# Peripheralls_and_power_Supply.net
KiCad netlist of a schematic drawn in Altium Designer
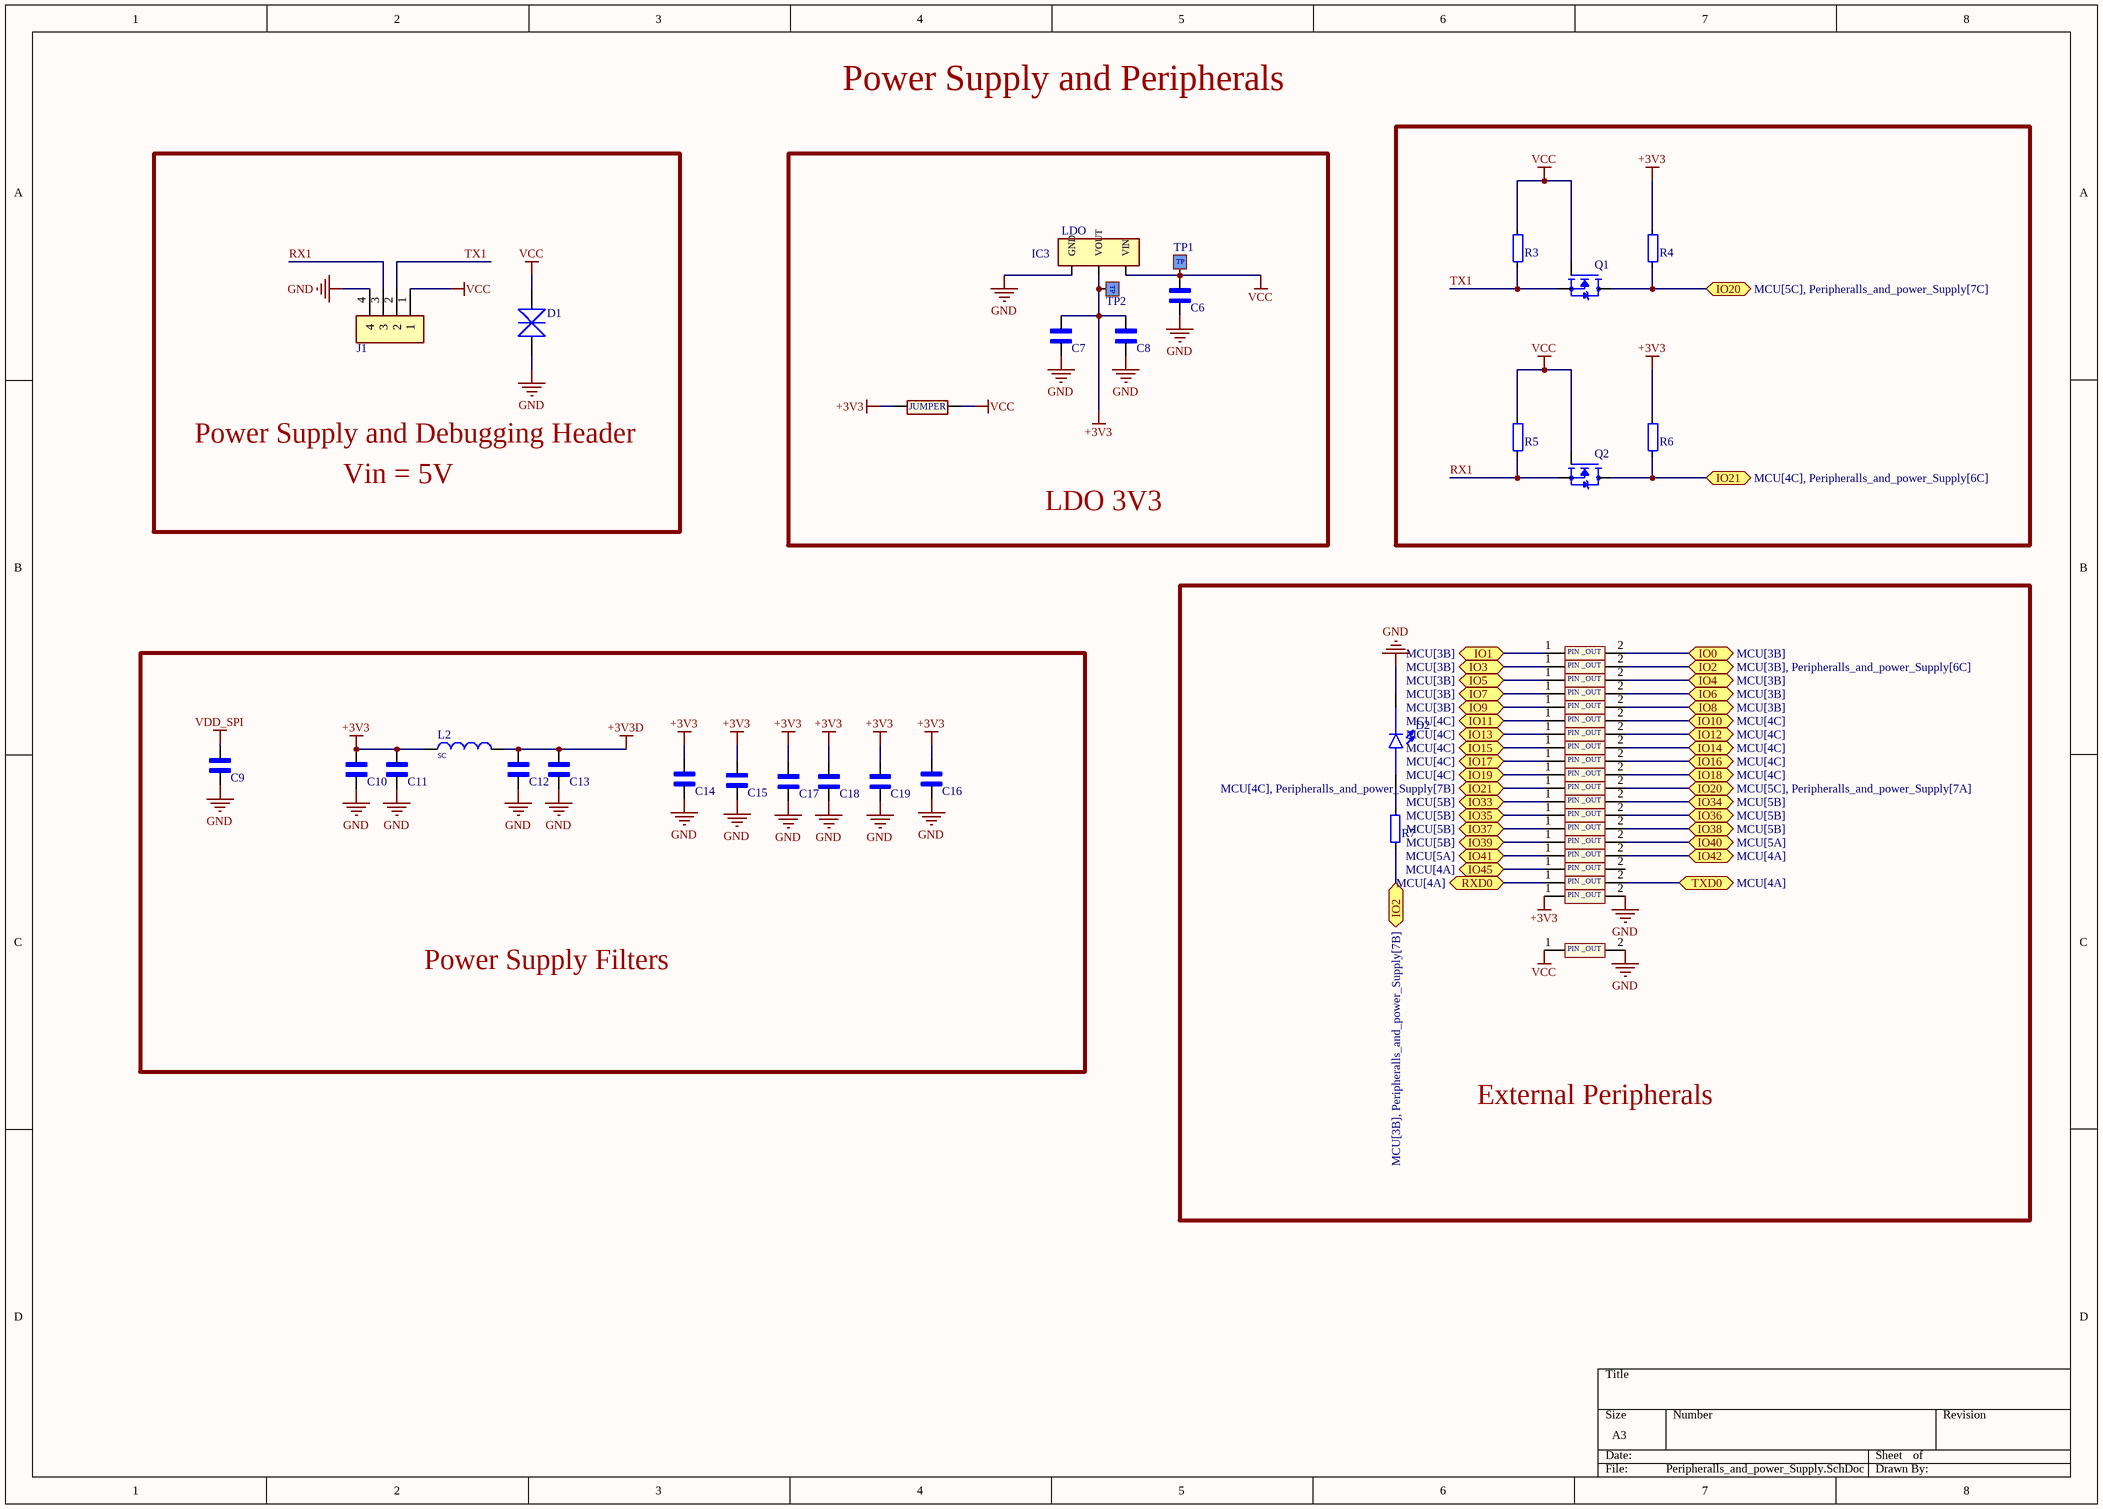
[diagram p0: Peripheralls_and_power_Supply.SchDoc]

(export (version "E")
  (design (tool "Eeschema 10.0.6"))
  (components
    (comp (ref "C6") (value "CAP_0603") (footprint "CAP_0603") (libsource (lib "ESP32-S2") (part "CAP_0603")))
    (comp (ref "C7") (value "CAP_0603") (footprint "CAP_0603") (libsource (lib "") (part "CAP_0603_1")))
    (comp (ref "C8") (value "CAP_0603") (footprint "CAP_0603") (libsource (lib "") (part "CAP_0603_1")))
    (comp (ref "C9") (value "CAP_0603") (footprint "CAP_0603") (libsource (lib "ESP32-S2") (part "CAP_0603")))
    (comp (ref "C10")
      (value "CAP_0603")
      (footprint "CAP_0603")
      (libsource (lib "ESP32-S2") (part "CAP_0603"))
    )
    (comp (ref "C11")
      (value "CAP_0603")
      (footprint "CAP_0603")
      (libsource (lib "ESP32-S2") (part "CAP_0603"))
    )
    (comp (ref "C12")
      (value "CAP_0603")
      (footprint "CAP_0603")
      (libsource (lib "ESP32-S2") (part "CAP_0603"))
    )
    (comp (ref "C13")
      (value "CAP_0603")
      (footprint "CAP_0603")
      (libsource (lib "ESP32-S2") (part "CAP_0603"))
    )
    (comp (ref "C14")
      (value "CAP_0603")
      (footprint "CAP_0603")
      (libsource (lib "ESP32-S2") (part "CAP_0603"))
    )
    (comp (ref "C15")
      (value "CAP_0603")
      (footprint "CAP_0603")
      (libsource (lib "ESP32-S2") (part "CAP_0603"))
    )
    (comp (ref "C16")
      (value "CAP_0603")
      (footprint "CAP_0603")
      (libsource (lib "ESP32-S2") (part "CAP_0603"))
    )
    (comp (ref "C17")
      (value "CAP_0603")
      (footprint "CAP_0603")
      (libsource (lib "ESP32-S2") (part "CAP_0603"))
    )
    (comp (ref "C18")
      (value "CAP_0603")
      (footprint "CAP_0603")
      (libsource (lib "ESP32-S2") (part "CAP_0603"))
    )
    (comp (ref "C19")
      (value "CAP_0603")
      (footprint "CAP_0603")
      (libsource (lib "ESP32-S2") (part "CAP_0603"))
    )
    (comp (ref "D1")
      (value "TVS_DIODE_3.6V")
      (footprint "ESD_DIODE")
      (libsource (lib "ESP32-S2") (part "TVS_DIODE_3.6V"))
    )
    (comp (ref "D2")
      (value "LED0603")
      (footprint "LED0603")
      (description "White LED Indication - Discrete 2.93V 0603 (1608 Metric)")
      (fields (field (name "MF") "Lite-On Inc.") (field (name "MP") "LTW-C191TS5"))
      (libsource (lib "ESP32-S2") (part "LED0603"))
    )
    (comp (ref "IC3")
      (value "LDO")
      (footprint "AMS1117")
      (description "Integrated Circuit")
      (fields (field (name "MANUFACTURER_PART_NUMBER") "AMS1117-3.3"))
      (libsource (lib "ESP32-S2") (part "AMS1117-3.3"))
    )
    (comp (ref "J1")
      (value "S4B-PH-SM4-TB_LF__SN_")
      (footprint "S4B-PH-SM4-TB")
      (description "Connector")
      (fields (field (name "MANUFACTURER_PART_NUMBER") "S4B-PH-SM4-TB(LF)(SN)"))
      (libsource (lib "ESP32-S2") (part "S4B-PH-SM4-TB_LF__SN_"))
    )
    (comp (ref "JU1")
      (value "JUMER")
      (footprint "JUMPER")
      (description "RES_0603")
      (libsource (lib "ESP32-S2") (part "JUMPER"))
    )
    (comp (ref "L2")
      (value "SC")
      (footprint "IND_0402")
      (description "Inductor RF Chip Multi-Layer 2nH 0.3nH 100MHz 8Q-Factor Air 900mA 90mOhm DCR 0402 Automotive T/R")
      (fields (field (name "MP") "LQG15HZ2N0S02D") (field (name "Comment") "IND_0402"))
      (libsource (lib "ESP32-S2") (part "IND_2.0nH_0402"))
    )
    (comp (ref "P1") (value "PIN OUT") (footprint "PIN_OUT") (libsource (lib "ESP32-S2") (part "PIN OUT")))
    (comp (ref "P2") (value "PIN OUT") (footprint "PIN_OUT") (libsource (lib "ESP32-S2") (part "PIN OUT")))
    (comp (ref "P3") (value "PIN OUT") (footprint "PIN_OUT") (libsource (lib "ESP32-S2") (part "PIN OUT")))
    (comp (ref "P4") (value "PIN OUT") (footprint "PIN_OUT") (libsource (lib "ESP32-S2") (part "PIN OUT")))
    (comp (ref "P5") (value "PIN OUT") (footprint "PIN_OUT") (libsource (lib "ESP32-S2") (part "PIN OUT")))
    (comp (ref "P6") (value "PIN OUT") (footprint "PIN_OUT") (libsource (lib "ESP32-S2") (part "PIN OUT")))
    (comp (ref "P7") (value "PIN OUT") (footprint "PIN_OUT") (libsource (lib "ESP32-S2") (part "PIN OUT")))
    (comp (ref "P8") (value "PIN OUT") (footprint "PIN_OUT") (libsource (lib "ESP32-S2") (part "PIN OUT")))
    (comp (ref "P9") (value "PIN OUT") (footprint "PIN_OUT") (libsource (lib "ESP32-S2") (part "PIN OUT")))
    (comp (ref "P10") (value "PIN OUT") (footprint "PIN_OUT") (libsource (lib "ESP32-S2") (part "PIN OUT")))
    (comp (ref "P11") (value "PIN OUT") (footprint "PIN_OUT") (libsource (lib "ESP32-S2") (part "PIN OUT")))
    (comp (ref "P12") (value "PIN OUT") (footprint "PIN_OUT") (libsource (lib "ESP32-S2") (part "PIN OUT")))
    (comp (ref "P13") (value "PIN OUT") (footprint "PIN_OUT") (libsource (lib "ESP32-S2") (part "PIN OUT")))
    (comp (ref "P14") (value "PIN OUT") (footprint "PIN_OUT") (libsource (lib "ESP32-S2") (part "PIN OUT")))
    (comp (ref "P15") (value "PIN OUT") (footprint "PIN_OUT") (libsource (lib "ESP32-S2") (part "PIN OUT")))
    (comp (ref "P16") (value "PIN OUT") (footprint "PIN_OUT") (libsource (lib "ESP32-S2") (part "PIN OUT")))
    (comp (ref "P17") (value "PIN OUT") (footprint "PIN_OUT") (libsource (lib "ESP32-S2") (part "PIN OUT")))
    (comp (ref "P18") (value "PIN OUT") (footprint "PIN_OUT") (libsource (lib "ESP32-S2") (part "PIN OUT")))
    (comp (ref "P19") (value "PIN OUT") (footprint "PIN_OUT") (libsource (lib "ESP32-S2") (part "PIN OUT")))
    (comp (ref "P20") (value "PIN OUT") (footprint "PIN_OUT") (libsource (lib "ESP32-S2") (part "PIN OUT")))
    (comp (ref "Q1")
      (value "LOGIC SHIFTER MOSFET")
      (footprint "BSS138_SOT-23-3 (TO-236)")
      (description "N-Channel 50V 220mA (Ta) 360mW (Ta) Surface Mount SOT-23-3")
      (fields (field (name "MP") "BSS138"))
      (libsource (lib "ESP32-S2") (part "BSS138"))
    )
    (comp (ref "Q2")
      (value "LOGIC SHIFTER MOSFET")
      (footprint "BSS138_SOT-23-3 (TO-236)")
      (description "N-Channel 50V 220mA (Ta) 360mW (Ta) Surface Mount SOT-23-3")
      (fields (field (name "MP") "BSS138"))
      (libsource (lib "ESP32-S2") (part "BSS138"))
    )
    (comp (ref "R3") (value "RES_0603") (footprint "RES_0603") (libsource (lib "ESP32-S2") (part "RES_0603")))
    (comp (ref "R4") (value "RES_0603") (footprint "RES_0603") (libsource (lib "ESP32-S2") (part "RES_0603")))
    (comp (ref "R5") (value "RES_0603") (footprint "RES_0603") (libsource (lib "ESP32-S2") (part "RES_0603")))
    (comp (ref "R6") (value "RES_0603") (footprint "RES_0603") (libsource (lib "ESP32-S2") (part "RES_0603")))
    (comp (ref "R7") (value "RES_0603") (footprint "RES_0603") (libsource (lib "ESP32-S2") (part "RES_0603")))
    (comp (ref "TP1") (value "TP") (footprint "PCBComponent_1") (libsource (lib "") (part "TP_1")))
    (comp (ref "TP2") (value "TP") (footprint "PCBComponent_1") (libsource (lib "ESP32-S2") (part "TP")))
  )
  (nets
    (net (code "1") (name "+3V3") (class "Default")
      (node (ref "C10") (pin "2") (pinfunction "2_2") (pintype "passive"))
      (node (ref "C11") (pin "2") (pinfunction "2_2") (pintype "passive"))
      (node (ref "C14") (pin "2") (pinfunction "2_2") (pintype "passive"))
      (node (ref "C15") (pin "2") (pinfunction "2_2") (pintype "passive"))
      (node (ref "C16") (pin "2") (pinfunction "2_2") (pintype "passive"))
      (node (ref "C17") (pin "2") (pinfunction "2_2") (pintype "passive"))
      (node (ref "C18") (pin "2") (pinfunction "2_2") (pintype "passive"))
      (node (ref "C19") (pin "2") (pinfunction "2_2") (pintype "passive"))
      (node (ref "C7") (pin "1") (pinfunction "1_1") (pintype "passive"))
      (node (ref "C8") (pin "1") (pinfunction "1_1") (pintype "passive"))
      (node (ref "IC3") (pin "2") (pinfunction "VOUT_2") (pintype "passive"))
      (node (ref "JU1") (pin "1") (pinfunction "1_1") (pintype "passive"))
      (node (ref "L2") (pin "1") (pinfunction "1_1") (pintype "passive"))
      (node (ref "P19") (pin "1") (pinfunction "1_1") (pintype "passive"))
      (node (ref "R4") (pin "2") (pinfunction "2_2") (pintype "passive"))
      (node (ref "R6") (pin "2") (pinfunction "2_2") (pintype "passive"))
      (node (ref "TP2") (pin "1") (pinfunction "T?_1") (pintype "passive"))
    )
    (net (code "2") (name "+3V3D") (class "Default")
      (node (ref "C12") (pin "2") (pinfunction "2_2") (pintype "passive"))
      (node (ref "C13") (pin "2") (pinfunction "2_2") (pintype "passive"))
      (node (ref "L2") (pin "2") (pinfunction "2_2") (pintype "passive"))
    )
    (net (code "3") (name "/IO0") (class "Default")
      (node (ref "P1") (pin "2") (pinfunction "2_2") (pintype "passive"))
    )
    (net (code "4") (name "/IO1") (class "Default")
      (node (ref "P1") (pin "1") (pinfunction "1_1") (pintype "passive"))
    )
    (net (code "5") (name "/IO2") (class "Default")
      (node (ref "P2") (pin "2") (pinfunction "2_2") (pintype "passive"))
      (node (ref "R7") (pin "2") (pinfunction "2_2") (pintype "passive"))
    )
    (net (code "6") (name "/IO3") (class "Default")
      (node (ref "P2") (pin "1") (pinfunction "1_1") (pintype "passive"))
    )
    (net (code "7") (name "/IO4") (class "Default")
      (node (ref "P3") (pin "2") (pinfunction "2_2") (pintype "passive"))
    )
    (net (code "8") (name "/IO5") (class "Default")
      (node (ref "P3") (pin "1") (pinfunction "1_1") (pintype "passive"))
    )
    (net (code "9") (name "/IO6") (class "Default")
      (node (ref "P4") (pin "2") (pinfunction "2_2") (pintype "passive"))
    )
    (net (code "10") (name "/IO7") (class "Default")
      (node (ref "P4") (pin "1") (pinfunction "1_1") (pintype "passive"))
    )
    (net (code "11") (name "/IO8") (class "Default")
      (node (ref "P5") (pin "2") (pinfunction "2_2") (pintype "passive"))
    )
    (net (code "12") (name "/IO9") (class "Default")
      (node (ref "P5") (pin "1") (pinfunction "1_1") (pintype "passive"))
    )
    (net (code "13") (name "/IO10") (class "Default")
      (node (ref "P6") (pin "2") (pinfunction "2_2") (pintype "passive"))
    )
    (net (code "14") (name "/IO11") (class "Default")
      (node (ref "P6") (pin "1") (pinfunction "1_1") (pintype "passive"))
    )
    (net (code "15") (name "/IO12") (class "Default")
      (node (ref "P7") (pin "2") (pinfunction "2_2") (pintype "passive"))
    )
    (net (code "16") (name "/IO13") (class "Default")
      (node (ref "P7") (pin "1") (pinfunction "1_1") (pintype "passive"))
    )
    (net (code "17") (name "/IO14") (class "Default")
      (node (ref "P8") (pin "2") (pinfunction "2_2") (pintype "passive"))
    )
    (net (code "18") (name "/IO15") (class "Default")
      (node (ref "P8") (pin "1") (pinfunction "1_1") (pintype "passive"))
    )
    (net (code "19") (name "/IO16") (class "Default")
      (node (ref "P9") (pin "2") (pinfunction "2_2") (pintype "passive"))
    )
    (net (code "20") (name "/IO17") (class "Default")
      (node (ref "P9") (pin "1") (pinfunction "1_1") (pintype "passive"))
    )
    (net (code "21") (name "/IO18") (class "Default")
      (node (ref "P10") (pin "2") (pinfunction "2_2") (pintype "passive"))
    )
    (net (code "22") (name "/IO19") (class "Default")
      (node (ref "P10") (pin "1") (pinfunction "1_1") (pintype "passive"))
    )
    (net (code "23") (name "/IO20") (class "Default")
      (node (ref "P11") (pin "2") (pinfunction "2_2") (pintype "passive"))
      (node (ref "Q1") (pin "3") (pinfunction "D_3") (pintype "passive"))
      (node (ref "R4") (pin "1") (pinfunction "1_1") (pintype "passive"))
    )
    (net (code "24") (name "/IO21") (class "Default")
      (node (ref "P11") (pin "1") (pinfunction "1_1") (pintype "passive"))
      (node (ref "Q2") (pin "3") (pinfunction "D_3") (pintype "passive"))
      (node (ref "R6") (pin "1") (pinfunction "1_1") (pintype "passive"))
    )
    (net (code "25") (name "/IO33") (class "Default")
      (node (ref "P12") (pin "1") (pinfunction "1_1") (pintype "passive"))
    )
    (net (code "26") (name "/IO34") (class "Default")
      (node (ref "P12") (pin "2") (pinfunction "2_2") (pintype "passive"))
    )
    (net (code "27") (name "/IO35") (class "Default")
      (node (ref "P13") (pin "1") (pinfunction "1_1") (pintype "passive"))
    )
    (net (code "28") (name "/IO36") (class "Default")
      (node (ref "P13") (pin "2") (pinfunction "2_2") (pintype "passive"))
    )
    (net (code "29") (name "/IO37") (class "Default")
      (node (ref "P14") (pin "1") (pinfunction "1_1") (pintype "passive"))
    )
    (net (code "30") (name "/IO38") (class "Default")
      (node (ref "P14") (pin "2") (pinfunction "2_2") (pintype "passive"))
    )
    (net (code "31") (name "/IO39") (class "Default")
      (node (ref "P15") (pin "1") (pinfunction "1_1") (pintype "passive"))
    )
    (net (code "32") (name "/IO40") (class "Default")
      (node (ref "P15") (pin "2") (pinfunction "2_2") (pintype "passive"))
    )
    (net (code "33") (name "/IO41") (class "Default")
      (node (ref "P16") (pin "1") (pinfunction "1_1") (pintype "passive"))
    )
    (net (code "34") (name "/IO42") (class "Default")
      (node (ref "P16") (pin "2") (pinfunction "2_2") (pintype "passive"))
    )
    (net (code "35") (name "/IO45") (class "Default")
      (node (ref "P17") (pin "1") (pinfunction "1_1") (pintype "passive"))
    )
    (net (code "36") (name "/RX1") (class "Default")
      (node (ref "J1") (pin "3") (pinfunction "3_3") (pintype "passive"))
      (node (ref "Q2") (pin "2") (pinfunction "S_2") (pintype "passive"))
      (node (ref "R5") (pin "1") (pinfunction "1_1") (pintype "passive"))
    )
    (net (code "37") (name "/RXD0") (class "Default")
      (node (ref "P18") (pin "1") (pinfunction "1_1") (pintype "passive"))
    )
    (net (code "38") (name "/TX1") (class "Default")
      (node (ref "J1") (pin "2") (pinfunction "2_2") (pintype "passive"))
      (node (ref "Q1") (pin "2") (pinfunction "S_2") (pintype "passive"))
      (node (ref "R3") (pin "1") (pinfunction "1_1") (pintype "passive"))
    )
    (net (code "39") (name "/TXD0") (class "Default")
      (node (ref "P18") (pin "2") (pinfunction "2_2") (pintype "passive"))
    )
    (net (code "40") (name "GND") (class "Default")
      (node (ref "C10") (pin "1") (pinfunction "1_1") (pintype "passive"))
      (node (ref "C11") (pin "1") (pinfunction "1_1") (pintype "passive"))
      (node (ref "C12") (pin "1") (pinfunction "1_1") (pintype "passive"))
      (node (ref "C13") (pin "1") (pinfunction "1_1") (pintype "passive"))
      (node (ref "C14") (pin "1") (pinfunction "1_1") (pintype "passive"))
      (node (ref "C15") (pin "1") (pinfunction "1_1") (pintype "passive"))
      (node (ref "C16") (pin "1") (pinfunction "1_1") (pintype "passive"))
      (node (ref "C17") (pin "1") (pinfunction "1_1") (pintype "passive"))
      (node (ref "C18") (pin "1") (pinfunction "1_1") (pintype "passive"))
      (node (ref "C19") (pin "1") (pinfunction "1_1") (pintype "passive"))
      (node (ref "C6") (pin "1") (pinfunction "1_1") (pintype "passive"))
      (node (ref "C7") (pin "2") (pinfunction "2_2") (pintype "passive"))
      (node (ref "C8") (pin "2") (pinfunction "2_2") (pintype "passive"))
      (node (ref "C9") (pin "1") (pinfunction "1_1") (pintype "passive"))
      (node (ref "D1") (pin "2") (pinfunction "2_2") (pintype "passive"))
      (node (ref "D2") (pin "C") (pinfunction "C_C") (pintype "passive"))
      (node (ref "IC3") (pin "1") (pinfunction "GND_1") (pintype "passive"))
      (node (ref "J1") (pin "4") (pinfunction "4_4") (pintype "passive"))
      (node (ref "P19") (pin "2") (pinfunction "2_2") (pintype "passive"))
      (node (ref "P20") (pin "2") (pinfunction "2_2") (pintype "passive"))
    )
    (net (code "41") (name "Net-(D2-PadA)") (class "Default")
      (node (ref "D2") (pin "A") (pinfunction "A_A") (pintype "passive"))
      (node (ref "R7") (pin "1") (pinfunction "1_1") (pintype "passive"))
    )
    (net (code "42") (name "VCC") (class "Default")
      (node (ref "C6") (pin "2") (pinfunction "2_2") (pintype "passive"))
      (node (ref "D1") (pin "1") (pinfunction "1_1") (pintype "passive"))
      (node (ref "IC3") (pin "3") (pinfunction "VIN_3") (pintype "passive"))
      (node (ref "J1") (pin "1") (pinfunction "1_1") (pintype "passive"))
      (node (ref "JU1") (pin "2") (pinfunction "2_2") (pintype "passive"))
      (node (ref "P20") (pin "1") (pinfunction "1_1") (pintype "passive"))
      (node (ref "Q1") (pin "1") (pinfunction "G_1") (pintype "passive"))
      (node (ref "Q2") (pin "1") (pinfunction "G_1") (pintype "passive"))
      (node (ref "R3") (pin "2") (pinfunction "2_2") (pintype "passive"))
      (node (ref "R5") (pin "2") (pinfunction "2_2") (pintype "passive"))
      (node (ref "TP1") (pin "1") (pinfunction "T?_1") (pintype "passive"))
    )
    (net (code "43") (name "VDD_SPI") (class "Default")
      (node (ref "C9") (pin "2") (pinfunction "2_2") (pintype "passive"))
    )
    (net (code "44") (name "unconnected-(P17-Pad2)") (class "Default")
      (node (ref "P17") (pin "2") (pinfunction "2_2") (pintype "passive"))
    )
  )
)
